# 2_MCU.net
KiCad netlist of a schematic drawn in Altium Designer
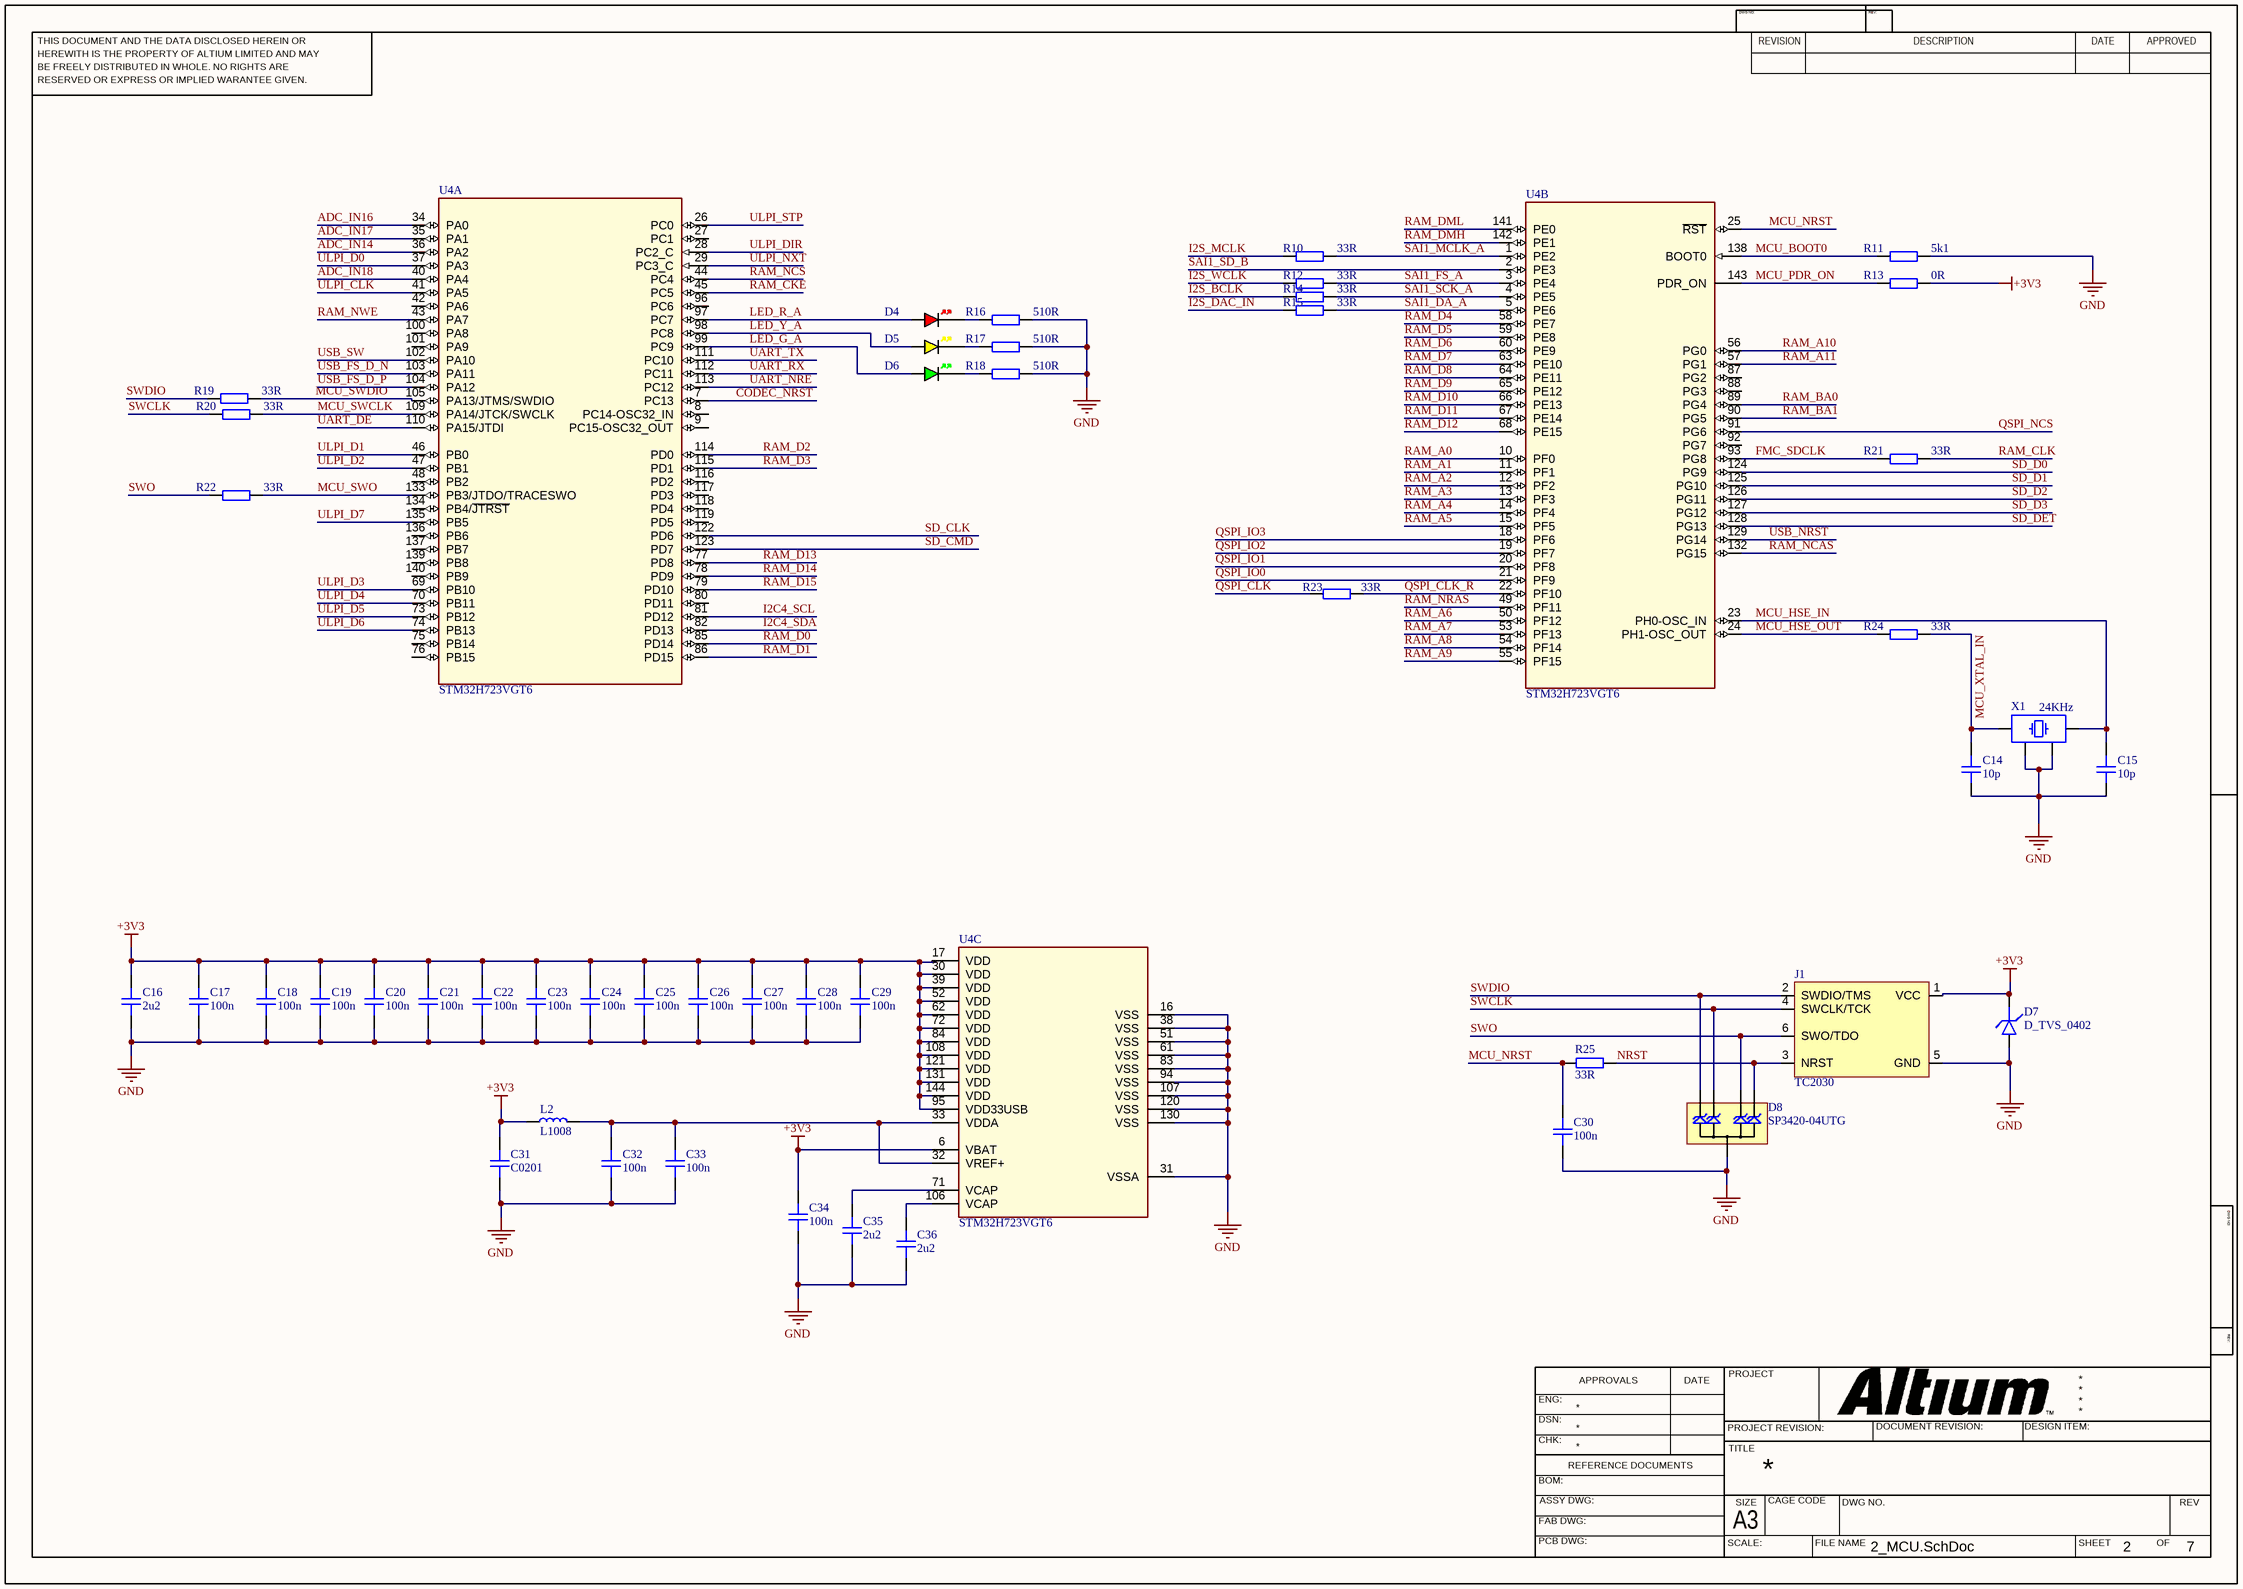
[diagram p0: 2_MCU.SchDoc]

(export (version "E")
  (design (tool "Eeschema 10.0.6"))
  (components
    (comp (ref "C14")
      (value "10p")
      (footprint "CAP_0201")
      (description "Capacitor SMD 0201")
      (libsource (lib "Schematic-Lib-PhilsLab") (part "CAP_0201"))
    )
    (comp (ref "C15")
      (value "10p")
      (footprint "CAP_0201")
      (description "Capacitor SMD 0201")
      (libsource (lib "Schematic-Lib-PhilsLab") (part "CAP_0201"))
    )
    (comp (ref "C16")
      (value "2u2")
      (footprint "CAP_0201")
      (description "Capacitor SMD 0201")
      (libsource (lib "Schematic-Lib-PhilsLab") (part "CAP_0201"))
    )
    (comp (ref "C17")
      (value "100n")
      (footprint "CAP_0201")
      (description "Capacitor SMD 0201")
      (libsource (lib "Schematic-Lib-PhilsLab") (part "CAP_0201"))
    )
    (comp (ref "C18")
      (value "100n")
      (footprint "CAP_0201")
      (description "Capacitor SMD 0201")
      (libsource (lib "Schematic-Lib-PhilsLab") (part "CAP_0201"))
    )
    (comp (ref "C19")
      (value "100n")
      (footprint "CAP_0201")
      (description "Capacitor SMD 0201")
      (libsource (lib "Schematic-Lib-PhilsLab") (part "CAP_0201"))
    )
    (comp (ref "C20")
      (value "100n")
      (footprint "CAP_0201")
      (description "Capacitor SMD 0201")
      (libsource (lib "Schematic-Lib-PhilsLab") (part "CAP_0201"))
    )
    (comp (ref "C21")
      (value "100n")
      (footprint "CAP_0201")
      (description "Capacitor SMD 0201")
      (libsource (lib "Schematic-Lib-PhilsLab") (part "CAP_0201"))
    )
    (comp (ref "C22")
      (value "100n")
      (footprint "CAP_0201")
      (description "Capacitor SMD 0201")
      (libsource (lib "Schematic-Lib-PhilsLab") (part "CAP_0201"))
    )
    (comp (ref "C23")
      (value "100n")
      (footprint "CAP_0201")
      (description "Capacitor SMD 0201")
      (libsource (lib "Schematic-Lib-PhilsLab") (part "CAP_0201"))
    )
    (comp (ref "C24")
      (value "100n")
      (footprint "CAP_0201")
      (description "Capacitor SMD 0201")
      (libsource (lib "Schematic-Lib-PhilsLab") (part "CAP_0201"))
    )
    (comp (ref "C25")
      (value "100n")
      (footprint "CAP_0201")
      (description "Capacitor SMD 0201")
      (libsource (lib "Schematic-Lib-PhilsLab") (part "CAP_0201"))
    )
    (comp (ref "C26")
      (value "100n")
      (footprint "CAP_0201")
      (description "Capacitor SMD 0201")
      (libsource (lib "Schematic-Lib-PhilsLab") (part "CAP_0201"))
    )
    (comp (ref "C27")
      (value "100n")
      (footprint "CAP_0201")
      (description "Capacitor SMD 0201")
      (libsource (lib "Schematic-Lib-PhilsLab") (part "CAP_0201"))
    )
    (comp (ref "C28")
      (value "100n")
      (footprint "CAP_0201")
      (description "Capacitor SMD 0201")
      (libsource (lib "Schematic-Lib-PhilsLab") (part "CAP_0201"))
    )
    (comp (ref "C29")
      (value "100n")
      (footprint "CAP_0201")
      (description "Capacitor SMD 0201")
      (libsource (lib "Schematic-Lib-PhilsLab") (part "CAP_0201"))
    )
    (comp (ref "C30")
      (value "100n")
      (footprint "CAP_0201")
      (description "Capacitor SMD 0201")
      (libsource (lib "Schematic-Lib-PhilsLab") (part "CAP_0201"))
    )
    (comp (ref "C31")
      (value "C0201")
      (footprint "CAP_0201")
      (description "Capacitor SMD 0201")
      (libsource (lib "Schematic-Lib-PhilsLab") (part "CAP_0201"))
    )
    (comp (ref "C32")
      (value "100n")
      (footprint "CAP_0201")
      (description "Capacitor SMD 0201")
      (libsource (lib "Schematic-Lib-PhilsLab") (part "CAP_0201"))
    )
    (comp (ref "C33")
      (value "100n")
      (footprint "CAP_0201")
      (description "Capacitor SMD 0201")
      (libsource (lib "Schematic-Lib-PhilsLab") (part "CAP_0201"))
    )
    (comp (ref "C34")
      (value "100n")
      (footprint "CAP_0201")
      (description "Capacitor SMD 0201")
      (libsource (lib "Schematic-Lib-PhilsLab") (part "CAP_0201"))
    )
    (comp (ref "C35")
      (value "2u2")
      (footprint "CAP_0201")
      (description "Capacitor SMD 0201")
      (libsource (lib "Schematic-Lib-PhilsLab") (part "CAP_0201"))
    )
    (comp (ref "C36")
      (value "2u2")
      (footprint "CAP_0201")
      (description "Capacitor SMD 0201")
      (libsource (lib "Schematic-Lib-PhilsLab") (part "CAP_0201"))
    )
    (comp (ref "D4")
      (value "RED")
      (footprint "LED_0603_RED")
      (description "LED 0603 RED SMD")
      (libsource (lib "Schematic-Lib-PhilsLab") (part "LED_0603_RED"))
    )
    (comp (ref "D5")
      (value "YELLOW")
      (footprint "LED_0603_YELLOW")
      (description "LED 0603 YELLOW SMD")
      (libsource (lib "Schematic-Lib-PhilsLab") (part "LED_0603_YELLOW"))
    )
    (comp (ref "D6")
      (value "GREEN")
      (footprint "LED_0603_GREEN")
      (description "LED 0603 GREEN SMD")
      (libsource (lib "Schematic-Lib-PhilsLab") (part "LED_0603_GREEN"))
    )
    (comp (ref "D7")
      (value "D_TVS_0402")
      (footprint "D_0402")
      (description "Diode TVS / ESD 0402")
      (libsource (lib "Schematic-Lib-PhilsLab") (part "D_TVS_0402"))
    )
    (comp (ref "D8")
      (value "SP3420-04UTG")
      (footprint "uDFN-10")
      (description "TVS Diode Array Low Capacitance ESD Protection 4-Channel (Vwork=3V3, Vclamp=6V)")
      (fields (field (name "MANUFACTURER") "Littelfuse"))
      (libsource (lib "Schematic-Lib-PhilsLab") (part "SP3420-04UTG"))
    )
    (comp (ref "J1")
      (value "TC2030")
      (footprint "TC2030-FP")
      (description "Tag-Connect No-Solder SWD Debug Connector DO NOT PLACE")
      (fields (field (name "MANUFACTURER") "Tag-Connect"))
      (libsource (lib "Schematic-Lib-PhilsLab") (part "TC2030"))
    )
    (comp (ref "L2")
      (value "L1008")
      (footprint "IND_1008")
      (description "Inductor SMD 1008")
      (libsource (lib "Schematic-Lib-PhilsLab") (part "IND_1008"))
    )
    (comp (ref "R10")
      (value "33R")
      (footprint "RES_0402")
      (description "Resistor SMD 0402")
      (libsource (lib "Schematic-Lib-PhilsLab") (part "RES_0402"))
    )
    (comp (ref "R11")
      (value "5k1")
      (footprint "RES_0402")
      (description "Resistor SMD 0402")
      (libsource (lib "Schematic-Lib-PhilsLab") (part "RES_0402"))
    )
    (comp (ref "R12")
      (value "33R")
      (footprint "RES_0402")
      (description "Resistor SMD 0402")
      (libsource (lib "Schematic-Lib-PhilsLab") (part "RES_0402"))
    )
    (comp (ref "R13")
      (value "0R")
      (footprint "RES_0402")
      (description "Resistor SMD 0402")
      (libsource (lib "Schematic-Lib-PhilsLab") (part "RES_0402"))
    )
    (comp (ref "R14")
      (value "33R")
      (footprint "RES_0402")
      (description "Resistor SMD 0402")
      (libsource (lib "Schematic-Lib-PhilsLab") (part "RES_0402"))
    )
    (comp (ref "R15")
      (value "33R")
      (footprint "RES_0402")
      (description "Resistor SMD 0402")
      (libsource (lib "Schematic-Lib-PhilsLab") (part "RES_0402"))
    )
    (comp (ref "R16")
      (value "510R")
      (footprint "RES_0402")
      (description "Resistor SMD 0402")
      (libsource (lib "Schematic-Lib-PhilsLab") (part "RES_0402"))
    )
    (comp (ref "R17")
      (value "510R")
      (footprint "RES_0402")
      (description "Resistor SMD 0402")
      (libsource (lib "Schematic-Lib-PhilsLab") (part "RES_0402"))
    )
    (comp (ref "R18")
      (value "510R")
      (footprint "RES_0402")
      (description "Resistor SMD 0402")
      (libsource (lib "Schematic-Lib-PhilsLab") (part "RES_0402"))
    )
    (comp (ref "R19")
      (value "33R")
      (footprint "RES_0402")
      (description "Resistor SMD 0402")
      (libsource (lib "Schematic-Lib-PhilsLab") (part "RES_0402"))
    )
    (comp (ref "R20")
      (value "33R")
      (footprint "RES_0402")
      (description "Resistor SMD 0402")
      (libsource (lib "Schematic-Lib-PhilsLab") (part "RES_0402"))
    )
    (comp (ref "R21")
      (value "33R")
      (footprint "RES_0402")
      (description "Resistor SMD 0402")
      (libsource (lib "Schematic-Lib-PhilsLab") (part "RES_0402"))
    )
    (comp (ref "R22")
      (value "33R")
      (footprint "RES_0402")
      (description "Resistor SMD 0402")
      (libsource (lib "Schematic-Lib-PhilsLab") (part "RES_0402"))
    )
    (comp (ref "R23")
      (value "33R")
      (footprint "RES_0402")
      (description "Resistor SMD 0402")
      (libsource (lib "Schematic-Lib-PhilsLab") (part "RES_0402"))
    )
    (comp (ref "R24")
      (value "33R")
      (footprint "RES_0402")
      (description "Resistor SMD 0402")
      (libsource (lib "Schematic-Lib-PhilsLab") (part "RES_0402"))
    )
    (comp (ref "R25")
      (value "33R")
      (footprint "RES_0402")
      (description "Resistor SMD 0402")
      (libsource (lib "Schematic-Lib-PhilsLab") (part "RES_0402"))
    )
    (comp (ref "U4")
      (value "STM32H723VGT6")
      (footprint "STM32H7")
      (libsource (lib "") (part "STM32H723VGT6_1"))
    )
    (comp (ref "X1")
      (value "24KHz")
      (footprint "XTAL_2520")
      (description "Crystal SMD 2520")
      (libsource (lib "Schematic-Lib-PhilsLab") (part "XTAL_2520"))
    )
  )
  (nets
    (net (code "1") (name "+3V3") (class "Default")
      (node (ref "C16") (pin "2") (pinfunction "2_2") (pintype "passive"))
      (node (ref "C17") (pin "2") (pinfunction "2_2") (pintype "passive"))
      (node (ref "C18") (pin "2") (pinfunction "2_2") (pintype "passive"))
      (node (ref "C19") (pin "2") (pinfunction "2_2") (pintype "passive"))
      (node (ref "C20") (pin "2") (pinfunction "2_2") (pintype "passive"))
      (node (ref "C21") (pin "2") (pinfunction "2_2") (pintype "passive"))
      (node (ref "C22") (pin "2") (pinfunction "2_2") (pintype "passive"))
      (node (ref "C23") (pin "2") (pinfunction "2_2") (pintype "passive"))
      (node (ref "C24") (pin "2") (pinfunction "2_2") (pintype "passive"))
      (node (ref "C25") (pin "2") (pinfunction "2_2") (pintype "passive"))
      (node (ref "C26") (pin "2") (pinfunction "2_2") (pintype "passive"))
      (node (ref "C27") (pin "2") (pinfunction "2_2") (pintype "passive"))
      (node (ref "C28") (pin "2") (pinfunction "2_2") (pintype "passive"))
      (node (ref "C29") (pin "2") (pinfunction "2_2") (pintype "passive"))
      (node (ref "C31") (pin "2") (pinfunction "2_2") (pintype "passive"))
      (node (ref "C34") (pin "2") (pinfunction "2_2") (pintype "passive"))
      (node (ref "D7") (pin "K") (pinfunction "K_K") (pintype "passive"))
      (node (ref "J1") (pin "1") (pinfunction "VCC_1") (pintype "passive"))
      (node (ref "L2") (pin "1") (pinfunction "1_1") (pintype "passive"))
      (node (ref "R13") (pin "2") (pinfunction "2_2") (pintype "passive"))
      (node (ref "U4") (pin "108") (pinfunction "VDD_108") (pintype "power_in"))
      (node (ref "U4") (pin "121") (pinfunction "VDD_121") (pintype "power_in"))
      (node (ref "U4") (pin "131") (pinfunction "VDD_131") (pintype "power_in"))
      (node (ref "U4") (pin "144") (pinfunction "VDD_144") (pintype "power_in"))
      (node (ref "U4") (pin "30") (pinfunction "VDD_30") (pintype "power_in"))
      (node (ref "U4") (pin "39") (pinfunction "VDD_39") (pintype "power_in"))
      (node (ref "U4") (pin "52") (pinfunction "VDD_52") (pintype "power_in"))
      (node (ref "U4") (pin "6") (pinfunction "VBAT_6") (pintype "power_in"))
      (node (ref "U4") (pin "62") (pinfunction "VDD_62") (pintype "power_in"))
      (node (ref "U4") (pin "72") (pinfunction "VDD_72") (pintype "power_in"))
      (node (ref "U4") (pin "84") (pinfunction "VDD_84") (pintype "power_in"))
      (node (ref "U4") (pin "95") (pinfunction "VDD33USB_95") (pintype "power_in"))
    )
    (net (code "2") (name "/ADC_IN14") (class "Default")
      (node (ref "U4") (pin "36") (pinfunction "PA2_36") (pintype "bidirectional"))
    )
    (net (code "3") (name "/ADC_IN16") (class "Default")
      (node (ref "U4") (pin "34") (pinfunction "PA0_34") (pintype "bidirectional"))
    )
    (net (code "4") (name "/ADC_IN17") (class "Default")
      (node (ref "U4") (pin "35") (pinfunction "PA1_35") (pintype "bidirectional"))
    )
    (net (code "5") (name "/ADC_IN18") (class "Default")
      (node (ref "U4") (pin "40") (pinfunction "PA4_40") (pintype "bidirectional"))
    )
    (net (code "6") (name "/CODEC_NRST") (class "Default")
      (node (ref "U4") (pin "7") (pinfunction "PC13_7") (pintype "bidirectional"))
    )
    (net (code "7") (name "/FMC_SDCLK") (class "Default")
      (node (ref "R21") (pin "1") (pinfunction "1_1") (pintype "passive"))
      (node (ref "U4") (pin "93") (pinfunction "PG8_93") (pintype "bidirectional"))
    )
    (net (code "8") (name "/I2C4_SCL") (class "Default")
      (node (ref "U4") (pin "81") (pinfunction "PD12_81") (pintype "bidirectional"))
    )
    (net (code "9") (name "/I2C4_SDA") (class "Default")
      (node (ref "U4") (pin "82") (pinfunction "PD13_82") (pintype "bidirectional"))
    )
    (net (code "10") (name "/I2S_BCLK") (class "Default")
      (node (ref "R14") (pin "1") (pinfunction "1_1") (pintype "passive"))
    )
    (net (code "11") (name "/I2S_DAC_IN") (class "Default")
      (node (ref "R15") (pin "1") (pinfunction "1_1") (pintype "passive"))
    )
    (net (code "12") (name "/I2S_MCLK") (class "Default")
      (node (ref "R10") (pin "1") (pinfunction "1_1") (pintype "passive"))
    )
    (net (code "13") (name "/I2S_WCLK") (class "Default")
      (node (ref "R12") (pin "1") (pinfunction "1_1") (pintype "passive"))
    )
    (net (code "14") (name "/LED_G_A") (class "Default")
      (node (ref "D6") (pin "A") (pinfunction "A_A") (pintype "passive"))
      (node (ref "U4") (pin "99") (pinfunction "PC9_99") (pintype "bidirectional"))
    )
    (net (code "15") (name "/LED_R_A") (class "Default")
      (node (ref "D4") (pin "A") (pinfunction "A_A") (pintype "passive"))
      (node (ref "U4") (pin "97") (pinfunction "PC7_97") (pintype "bidirectional"))
    )
    (net (code "16") (name "/LED_Y_A") (class "Default")
      (node (ref "D5") (pin "A") (pinfunction "A_A") (pintype "passive"))
      (node (ref "U4") (pin "98") (pinfunction "PC8_98") (pintype "bidirectional"))
    )
    (net (code "17") (name "/MCU_BOOT0") (class "Default")
      (node (ref "R11") (pin "1") (pinfunction "1_1") (pintype "passive"))
      (node (ref "U4") (pin "138") (pinfunction "BOOT0_138") (pintype "input"))
    )
    (net (code "18") (name "/MCU_HSE_IN") (class "Default")
      (node (ref "C15") (pin "2") (pinfunction "2_2") (pintype "passive"))
      (node (ref "U4") (pin "23") (pinfunction "PH0-OSC_IN_23") (pintype "bidirectional"))
      (node (ref "X1") (pin "3") (pinfunction "3_3") (pintype "passive"))
    )
    (net (code "19") (name "/MCU_HSE_OUT") (class "Default")
      (node (ref "R24") (pin "1") (pinfunction "1_1") (pintype "passive"))
      (node (ref "U4") (pin "24") (pinfunction "PH1-OSC_OUT_24") (pintype "bidirectional"))
    )
    (net (code "20") (name "/MCU_NRST") (class "Default")
      (node (ref "C30") (pin "2") (pinfunction "2_2") (pintype "passive"))
      (node (ref "R25") (pin "1") (pinfunction "1_1") (pintype "passive"))
      (node (ref "U4") (pin "25") (pinfunction "~{RST}_25") (pintype "bidirectional"))
    )
    (net (code "21") (name "/MCU_PDR_ON") (class "Default")
      (node (ref "R13") (pin "1") (pinfunction "1_1") (pintype "passive"))
      (node (ref "U4") (pin "143") (pinfunction "PDR_ON_143") (pintype "power_in"))
    )
    (net (code "22") (name "/MCU_SWCLK") (class "Default")
      (node (ref "R20") (pin "2") (pinfunction "2_2") (pintype "passive"))
      (node (ref "U4") (pin "109") (pinfunction "PA14/JTCK/SWCLK_109") (pintype "bidirectional"))
    )
    (net (code "23") (name "/MCU_SWDIO") (class "Default")
      (node (ref "R19") (pin "2") (pinfunction "2_2") (pintype "passive"))
      (node (ref "U4") (pin "105") (pinfunction "PA13/JTMS/SWDIO_105") (pintype "bidirectional"))
    )
    (net (code "24") (name "/MCU_SWO") (class "Default")
      (node (ref "R22") (pin "2") (pinfunction "2_2") (pintype "passive"))
      (node (ref "U4") (pin "133") (pinfunction "PB3/JTDO/TRACESWO_133") (pintype "bidirectional"))
    )
    (net (code "25") (name "/MCU_XTAL_IN") (class "Default")
      (node (ref "C14") (pin "2") (pinfunction "2_2") (pintype "passive"))
      (node (ref "R24") (pin "2") (pinfunction "2_2") (pintype "passive"))
      (node (ref "X1") (pin "1") (pinfunction "1_1") (pintype "passive"))
    )
    (net (code "26") (name "/NRST") (class "Default")
      (node (ref "D8") (pin "56") (pintype "passive"))
      (node (ref "J1") (pin "3") (pinfunction "NRST_3") (pintype "passive"))
      (node (ref "R25") (pin "2") (pinfunction "2_2") (pintype "passive"))
    )
    (net (code "27") (name "/QSPI_CLK") (class "Default")
      (node (ref "R23") (pin "1") (pinfunction "1_1") (pintype "passive"))
    )
    (net (code "28") (name "/QSPI_CLK_R") (class "Default")
      (node (ref "R23") (pin "2") (pinfunction "2_2") (pintype "passive"))
      (node (ref "U4") (pin "22") (pinfunction "PF10_22") (pintype "bidirectional"))
    )
    (net (code "29") (name "/QSPI_IO0") (class "Default")
      (node (ref "U4") (pin "21") (pinfunction "PF9_21") (pintype "bidirectional"))
    )
    (net (code "30") (name "/QSPI_IO1") (class "Default")
      (node (ref "U4") (pin "20") (pinfunction "PF8_20") (pintype "bidirectional"))
    )
    (net (code "31") (name "/QSPI_IO2") (class "Default")
      (node (ref "U4") (pin "19") (pinfunction "PF7_19") (pintype "bidirectional"))
    )
    (net (code "32") (name "/QSPI_IO3") (class "Default")
      (node (ref "U4") (pin "18") (pinfunction "PF6_18") (pintype "bidirectional"))
    )
    (net (code "33") (name "/QSPI_NCS") (class "Default")
      (node (ref "U4") (pin "91") (pinfunction "PG6_91") (pintype "bidirectional"))
    )
    (net (code "34") (name "/RAM_A0") (class "Default")
      (node (ref "U4") (pin "10") (pinfunction "PF0_10") (pintype "bidirectional"))
    )
    (net (code "35") (name "/RAM_A1") (class "Default")
      (node (ref "U4") (pin "11") (pinfunction "PF1_11") (pintype "bidirectional"))
    )
    (net (code "36") (name "/RAM_A2") (class "Default")
      (node (ref "U4") (pin "12") (pinfunction "PF2_12") (pintype "bidirectional"))
    )
    (net (code "37") (name "/RAM_A3") (class "Default")
      (node (ref "U4") (pin "13") (pinfunction "PF3_13") (pintype "bidirectional"))
    )
    (net (code "38") (name "/RAM_A4") (class "Default")
      (node (ref "U4") (pin "14") (pinfunction "PF4_14") (pintype "bidirectional"))
    )
    (net (code "39") (name "/RAM_A5") (class "Default")
      (node (ref "U4") (pin "15") (pinfunction "PF5_15") (pintype "bidirectional"))
    )
    (net (code "40") (name "/RAM_A6") (class "Default")
      (node (ref "U4") (pin "50") (pinfunction "PF12_50") (pintype "bidirectional"))
    )
    (net (code "41") (name "/RAM_A7") (class "Default")
      (node (ref "U4") (pin "53") (pinfunction "PF13_53") (pintype "bidirectional"))
    )
    (net (code "42") (name "/RAM_A8") (class "Default")
      (node (ref "U4") (pin "54") (pinfunction "PF14_54") (pintype "bidirectional"))
    )
    (net (code "43") (name "/RAM_A9") (class "Default")
      (node (ref "U4") (pin "55") (pinfunction "PF15_55") (pintype "bidirectional"))
    )
    (net (code "44") (name "/RAM_A10") (class "Default")
      (node (ref "U4") (pin "56") (pinfunction "PG0_56") (pintype "bidirectional"))
    )
    (net (code "45") (name "/RAM_A11") (class "Default")
      (node (ref "U4") (pin "57") (pinfunction "PG1_57") (pintype "bidirectional"))
    )
    (net (code "46") (name "/RAM_BA0") (class "Default")
      (node (ref "U4") (pin "89") (pinfunction "PG4_89") (pintype "bidirectional"))
    )
    (net (code "47") (name "/RAM_BA1") (class "Default")
      (node (ref "U4") (pin "90") (pinfunction "PG5_90") (pintype "bidirectional"))
    )
    (net (code "48") (name "/RAM_CKE") (class "Default")
      (node (ref "U4") (pin "45") (pinfunction "PC5_45") (pintype "bidirectional"))
    )
    (net (code "49") (name "/RAM_CLK") (class "Default")
      (node (ref "R21") (pin "2") (pinfunction "2_2") (pintype "passive"))
    )
    (net (code "50") (name "/RAM_D0") (class "Default")
      (node (ref "U4") (pin "85") (pinfunction "PD14_85") (pintype "bidirectional"))
    )
    (net (code "51") (name "/RAM_D1") (class "Default")
      (node (ref "U4") (pin "86") (pinfunction "PD15_86") (pintype "bidirectional"))
    )
    (net (code "52") (name "/RAM_D2") (class "Default")
      (node (ref "U4") (pin "114") (pinfunction "PD0_114") (pintype "bidirectional"))
    )
    (net (code "53") (name "/RAM_D3") (class "Default")
      (node (ref "U4") (pin "115") (pinfunction "PD1_115") (pintype "bidirectional"))
    )
    (net (code "54") (name "/RAM_D4") (class "Default")
      (node (ref "U4") (pin "58") (pinfunction "PE7_58") (pintype "bidirectional"))
    )
    (net (code "55") (name "/RAM_D5") (class "Default")
      (node (ref "U4") (pin "59") (pinfunction "PE8_59") (pintype "bidirectional"))
    )
    (net (code "56") (name "/RAM_D6") (class "Default")
      (node (ref "U4") (pin "60") (pinfunction "PE9_60") (pintype "bidirectional"))
    )
    (net (code "57") (name "/RAM_D7") (class "Default")
      (node (ref "U4") (pin "63") (pinfunction "PE10_63") (pintype "bidirectional"))
    )
    (net (code "58") (name "/RAM_D8") (class "Default")
      (node (ref "U4") (pin "64") (pinfunction "PE11_64") (pintype "bidirectional"))
    )
    (net (code "59") (name "/RAM_D9") (class "Default")
      (node (ref "U4") (pin "65") (pinfunction "PE12_65") (pintype "bidirectional"))
    )
    (net (code "60") (name "/RAM_D10") (class "Default")
      (node (ref "U4") (pin "66") (pinfunction "PE13_66") (pintype "bidirectional"))
    )
    (net (code "61") (name "/RAM_D11") (class "Default")
      (node (ref "U4") (pin "67") (pinfunction "PE14_67") (pintype "bidirectional"))
    )
    (net (code "62") (name "/RAM_D12") (class "Default")
      (node (ref "U4") (pin "68") (pinfunction "PE15_68") (pintype "bidirectional"))
    )
    (net (code "63") (name "/RAM_D13") (class "Default")
      (node (ref "U4") (pin "77") (pinfunction "PD8_77") (pintype "bidirectional"))
    )
    (net (code "64") (name "/RAM_D14") (class "Default")
      (node (ref "U4") (pin "78") (pinfunction "PD9_78") (pintype "bidirectional"))
    )
    (net (code "65") (name "/RAM_D15") (class "Default")
      (node (ref "U4") (pin "79") (pinfunction "PD10_79") (pintype "bidirectional"))
    )
    (net (code "66") (name "/RAM_DMH") (class "Default")
      (node (ref "U4") (pin "142") (pinfunction "PE1_142") (pintype "bidirectional"))
    )
    (net (code "67") (name "/RAM_DML") (class "Default")
      (node (ref "U4") (pin "141") (pinfunction "PE0_141") (pintype "bidirectional"))
    )
    (net (code "68") (name "/RAM_NCAS") (class "Default")
      (node (ref "U4") (pin "132") (pinfunction "PG15_132") (pintype "bidirectional"))
    )
    (net (code "69") (name "/RAM_NCS") (class "Default")
      (node (ref "U4") (pin "44") (pinfunction "PC4_44") (pintype "bidirectional"))
    )
    (net (code "70") (name "/RAM_NRAS") (class "Default")
      (node (ref "U4") (pin "49") (pinfunction "PF11_49") (pintype "bidirectional"))
    )
    (net (code "71") (name "/RAM_NWE") (class "Default")
      (node (ref "U4") (pin "43") (pinfunction "PA7_43") (pintype "bidirectional"))
    )
    (net (code "72") (name "/SAI1_DA_A") (class "Default")
      (node (ref "R15") (pin "2") (pinfunction "2_2") (pintype "passive"))
      (node (ref "U4") (pin "5") (pinfunction "PE6_5") (pintype "bidirectional"))
    )
    (net (code "73") (name "/SAI1_FS_A") (class "Default")
      (node (ref "R12") (pin "2") (pinfunction "2_2") (pintype "passive"))
      (node (ref "U4") (pin "3") (pinfunction "PE4_3") (pintype "bidirectional"))
    )
    (net (code "74") (name "/SAI1_MCLK_A") (class "Default")
      (node (ref "R10") (pin "2") (pinfunction "2_2") (pintype "passive"))
      (node (ref "U4") (pin "1") (pinfunction "PE2_1") (pintype "bidirectional"))
    )
    (net (code "75") (name "/SAI1_SCK_A") (class "Default")
      (node (ref "R14") (pin "2") (pinfunction "2_2") (pintype "passive"))
      (node (ref "U4") (pin "4") (pinfunction "PE5_4") (pintype "bidirectional"))
    )
    (net (code "76") (name "/SAI1_SD_B") (class "Default")
      (node (ref "U4") (pin "2") (pinfunction "PE3_2") (pintype "bidirectional"))
    )
    (net (code "77") (name "/SD_CLK") (class "Default")
      (node (ref "U4") (pin "122") (pinfunction "PD6_122") (pintype "bidirectional"))
    )
    (net (code "78") (name "/SD_CMD") (class "Default")
      (node (ref "U4") (pin "123") (pinfunction "PD7_123") (pintype "bidirectional"))
    )
    (net (code "79") (name "/SD_D0") (class "Default")
      (node (ref "U4") (pin "124") (pinfunction "PG9_124") (pintype "bidirectional"))
    )
    (net (code "80") (name "/SD_D1") (class "Default")
      (node (ref "U4") (pin "125") (pinfunction "PG10_125") (pintype "bidirectional"))
    )
    (net (code "81") (name "/SD_D2") (class "Default")
      (node (ref "U4") (pin "126") (pinfunction "PG11_126") (pintype "bidirectional"))
    )
    (net (code "82") (name "/SD_D3") (class "Default")
      (node (ref "U4") (pin "127") (pinfunction "PG12_127") (pintype "bidirectional"))
    )
    (net (code "83") (name "/SD_DET") (class "Default")
      (node (ref "U4") (pin "128") (pinfunction "PG13_128") (pintype "bidirectional"))
    )
    (net (code "84") (name "/SWCLK") (class "Default")
      (node (ref "D8") (pin "29") (pintype "passive"))
      (node (ref "J1") (pin "4") (pinfunction "SWCLK/TCK_4") (pintype "passive"))
      (node (ref "R20") (pin "1") (pinfunction "1_1") (pintype "passive"))
    )
    (net (code "85") (name "/SWDIO") (class "Default")
      (node (ref "D8") (pin "110") (pintype "passive"))
      (node (ref "J1") (pin "2") (pinfunction "SWDIO/TMS_2") (pintype "passive"))
      (node (ref "R19") (pin "1") (pinfunction "1_1") (pintype "passive"))
    )
    (net (code "86") (name "/SWO") (class "Default")
      (node (ref "D8") (pin "47") (pintype "passive"))
      (node (ref "J1") (pin "6") (pinfunction "SWO/TDO_6") (pintype "passive"))
      (node (ref "R22") (pin "1") (pinfunction "1_1") (pintype "passive"))
    )
    (net (code "87") (name "/UART_DE") (class "Default")
      (node (ref "U4") (pin "110") (pinfunction "PA15/JTDI_110") (pintype "bidirectional"))
    )
    (net (code "88") (name "/UART_NRE") (class "Default")
      (node (ref "U4") (pin "113") (pinfunction "PC12_113") (pintype "bidirectional"))
    )
    (net (code "89") (name "/UART_RX") (class "Default")
      (node (ref "U4") (pin "112") (pinfunction "PC11_112") (pintype "bidirectional"))
    )
    (net (code "90") (name "/UART_TX") (class "Default")
      (node (ref "U4") (pin "111") (pinfunction "PC10_111") (pintype "bidirectional"))
    )
    (net (code "91") (name "/ULPI_CLK") (class "Default")
      (node (ref "U4") (pin "41") (pinfunction "PA5_41") (pintype "bidirectional"))
    )
    (net (code "92") (name "/ULPI_D0") (class "Default")
      (node (ref "U4") (pin "37") (pinfunction "PA3_37") (pintype "bidirectional"))
    )
    (net (code "93") (name "/ULPI_D1") (class "Default")
      (node (ref "U4") (pin "46") (pinfunction "PB0_46") (pintype "bidirectional"))
    )
    (net (code "94") (name "/ULPI_D2") (class "Default")
      (node (ref "U4") (pin "47") (pinfunction "PB1_47") (pintype "bidirectional"))
    )
    (net (code "95") (name "/ULPI_D3") (class "Default")
      (node (ref "U4") (pin "69") (pinfunction "PB10_69") (pintype "bidirectional"))
    )
    (net (code "96") (name "/ULPI_D4") (class "Default")
      (node (ref "U4") (pin "70") (pinfunction "PB11_70") (pintype "bidirectional"))
    )
    (net (code "97") (name "/ULPI_D5") (class "Default")
      (node (ref "U4") (pin "73") (pinfunction "PB12_73") (pintype "bidirectional"))
    )
    (net (code "98") (name "/ULPI_D6") (class "Default")
      (node (ref "U4") (pin "74") (pinfunction "PB13_74") (pintype "bidirectional"))
    )
    (net (code "99") (name "/ULPI_D7") (class "Default")
      (node (ref "U4") (pin "135") (pinfunction "PB5_135") (pintype "bidirectional"))
    )
    (net (code "100") (name "/ULPI_DIR") (class "Default")
      (node (ref "U4") (pin "28") (pinfunction "PC2_C_28") (pintype "input"))
    )
    (net (code "101") (name "/ULPI_NXT") (class "Default")
      (node (ref "U4") (pin "29") (pinfunction "PC3_C_29") (pintype "input"))
    )
    (net (code "102") (name "/ULPI_STP") (class "Default")
      (node (ref "U4") (pin "26") (pinfunction "PC0_26") (pintype "bidirectional"))
    )
    (net (code "103") (name "/USB_FS_D_N") (class "Default")
      (node (ref "U4") (pin "103") (pinfunction "PA11_103") (pintype "bidirectional"))
    )
    (net (code "104") (name "/USB_FS_D_P") (class "Default")
      (node (ref "U4") (pin "104") (pinfunction "PA12_104") (pintype "bidirectional"))
    )
    (net (code "105") (name "/USB_NRST") (class "Default")
      (node (ref "U4") (pin "129") (pinfunction "PG14_129") (pintype "bidirectional"))
    )
    (net (code "106") (name "/USB_SW") (class "Default")
      (node (ref "U4") (pin "102") (pinfunction "PA10_102") (pintype "bidirectional"))
    )
    (net (code "107") (name "GND") (class "Default")
      (node (ref "C14") (pin "1") (pinfunction "1_1") (pintype "passive"))
      (node (ref "C15") (pin "1") (pinfunction "1_1") (pintype "passive"))
      (node (ref "C16") (pin "1") (pinfunction "1_1") (pintype "passive"))
      (node (ref "C17") (pin "1") (pinfunction "1_1") (pintype "passive"))
      (node (ref "C18") (pin "1") (pinfunction "1_1") (pintype "passive"))
      (node (ref "C19") (pin "1") (pinfunction "1_1") (pintype "passive"))
      (node (ref "C20") (pin "1") (pinfunction "1_1") (pintype "passive"))
      (node (ref "C21") (pin "1") (pinfunction "1_1") (pintype "passive"))
      (node (ref "C22") (pin "1") (pinfunction "1_1") (pintype "passive"))
      (node (ref "C23") (pin "1") (pinfunction "1_1") (pintype "passive"))
      (node (ref "C24") (pin "1") (pinfunction "1_1") (pintype "passive"))
      (node (ref "C25") (pin "1") (pinfunction "1_1") (pintype "passive"))
      (node (ref "C26") (pin "1") (pinfunction "1_1") (pintype "passive"))
      (node (ref "C27") (pin "1") (pinfunction "1_1") (pintype "passive"))
      (node (ref "C28") (pin "1") (pinfunction "1_1") (pintype "passive"))
      (node (ref "C29") (pin "1") (pinfunction "1_1") (pintype "passive"))
      (node (ref "C30") (pin "1") (pinfunction "1_1") (pintype "passive"))
      (node (ref "C31") (pin "1") (pinfunction "1_1") (pintype "passive"))
      (node (ref "C32") (pin "1") (pinfunction "1_1") (pintype "passive"))
      (node (ref "C33") (pin "1") (pinfunction "1_1") (pintype "passive"))
      (node (ref "C34") (pin "1") (pinfunction "1_1") (pintype "passive"))
      (node (ref "C35") (pin "1") (pinfunction "1_1") (pintype "passive"))
      (node (ref "C36") (pin "1") (pinfunction "1_1") (pintype "passive"))
      (node (ref "D7") (pin "A") (pinfunction "A_A") (pintype "passive"))
      (node (ref "D8") (pin "38") (pinfunction "GND_38") (pintype "passive"))
      (node (ref "J1") (pin "5") (pinfunction "GND_5") (pintype "passive"))
      (node (ref "R11") (pin "2") (pinfunction "2_2") (pintype "passive"))
      (node (ref "R16") (pin "2") (pinfunction "2_2") (pintype "passive"))
      (node (ref "R17") (pin "2") (pinfunction "2_2") (pintype "passive"))
      (node (ref "R18") (pin "2") (pinfunction "2_2") (pintype "passive"))
      (node (ref "U4") (pin "107") (pinfunction "VSS_107") (pintype "power_in"))
      (node (ref "U4") (pin "120") (pinfunction "VSS_120") (pintype "power_in"))
      (node (ref "U4") (pin "130") (pinfunction "VSS_130") (pintype "power_in"))
      (node (ref "U4") (pin "16") (pinfunction "VSS_16") (pintype "power_in"))
      (node (ref "U4") (pin "31") (pinfunction "VSSA_31") (pintype "power_in"))
      (node (ref "U4") (pin "38") (pinfunction "VSS_38") (pintype "power_in"))
      (node (ref "U4") (pin "51") (pinfunction "VSS_51") (pintype "power_in"))
      (node (ref "U4") (pin "61") (pinfunction "VSS_61") (pintype "power_in"))
      (node (ref "U4") (pin "83") (pinfunction "VSS_83") (pintype "power_in"))
      (node (ref "U4") (pin "94") (pinfunction "VSS_94") (pintype "power_in"))
      (node (ref "X1") (pin "2") (pinfunction "2_2") (pintype "passive"))
      (node (ref "X1") (pin "4") (pinfunction "4_4") (pintype "passive"))
    )
    (net (code "108") (name "Net-(C35-Pad2)") (class "Default")
      (node (ref "C35") (pin "2") (pinfunction "2_2") (pintype "passive"))
      (node (ref "U4") (pin "71") (pinfunction "VCAP_71") (pintype "power_in"))
    )
    (net (code "109") (name "Net-(C36-Pad2)") (class "Default")
      (node (ref "C36") (pin "2") (pinfunction "2_2") (pintype "passive"))
      (node (ref "U4") (pin "106") (pinfunction "VCAP_106") (pintype "power_in"))
    )
    (net (code "110") (name "Net-(D4-PadK)") (class "Default")
      (node (ref "D4") (pin "K") (pinfunction "K_K") (pintype "passive"))
      (node (ref "R16") (pin "1") (pinfunction "1_1") (pintype "passive"))
    )
    (net (code "111") (name "Net-(D5-PadK)") (class "Default")
      (node (ref "D5") (pin "K") (pinfunction "K_K") (pintype "passive"))
      (node (ref "R17") (pin "1") (pinfunction "1_1") (pintype "passive"))
    )
    (net (code "112") (name "Net-(D6-PadK)") (class "Default")
      (node (ref "D6") (pin "K") (pinfunction "K_K") (pintype "passive"))
      (node (ref "R18") (pin "1") (pinfunction "1_1") (pintype "passive"))
    )
    (net (code "113") (name "Net-(U4C-VDDA)") (class "Default")
      (node (ref "C32") (pin "2") (pinfunction "2_2") (pintype "passive"))
      (node (ref "C33") (pin "2") (pinfunction "2_2") (pintype "passive"))
      (node (ref "L2") (pin "2") (pinfunction "2_2") (pintype "passive"))
      (node (ref "U4") (pin "32") (pinfunction "VREF+_32") (pintype "power_in"))
      (node (ref "U4") (pin "33") (pinfunction "VDDA_33") (pintype "power_in"))
    )
    (net (code "114") (name "unconnected-(U4A-PA6-Pad42)") (class "Default")
      (node (ref "U4") (pin "42") (pinfunction "PA6_42") (pintype "bidirectional"))
    )
    (net (code "115") (name "unconnected-(U4A-PA8-Pad100)") (class "Default")
      (node (ref "U4") (pin "100") (pinfunction "PA8_100") (pintype "bidirectional"))
    )
    (net (code "116") (name "unconnected-(U4A-PA9-Pad101)") (class "Default")
      (node (ref "U4") (pin "101") (pinfunction "PA9_101") (pintype "bidirectional"))
    )
    (net (code "117") (name "unconnected-(U4A-PB2-Pad48)") (class "Default")
      (node (ref "U4") (pin "48") (pinfunction "PB2_48") (pintype "bidirectional"))
    )
    (net (code "118") (name "unconnected-(U4A-PB4{slash}~{JTRST}-Pad134)") (class "Default")
      (node (ref "U4") (pin "134") (pinfunction "PB4/~{JTRST}_134") (pintype "bidirectional"))
    )
    (net (code "119") (name "unconnected-(U4A-PB6-Pad136)") (class "Default")
      (node (ref "U4") (pin "136") (pinfunction "PB6_136") (pintype "bidirectional"))
    )
    (net (code "120") (name "unconnected-(U4A-PB7-Pad137)") (class "Default")
      (node (ref "U4") (pin "137") (pinfunction "PB7_137") (pintype "bidirectional"))
    )
    (net (code "121") (name "unconnected-(U4A-PB8-Pad139)") (class "Default")
      (node (ref "U4") (pin "139") (pinfunction "PB8_139") (pintype "bidirectional"))
    )
    (net (code "122") (name "unconnected-(U4A-PB9-Pad140)") (class "Default")
      (node (ref "U4") (pin "140") (pinfunction "PB9_140") (pintype "bidirectional"))
    )
    (net (code "123") (name "unconnected-(U4A-PB14-Pad75)") (class "Default")
      (node (ref "U4") (pin "75") (pinfunction "PB14_75") (pintype "bidirectional"))
    )
    (net (code "124") (name "unconnected-(U4A-PB15-Pad76)") (class "Default")
      (node (ref "U4") (pin "76") (pinfunction "PB15_76") (pintype "bidirectional"))
    )
    (net (code "125") (name "unconnected-(U4A-PC1-Pad27)") (class "Default")
      (node (ref "U4") (pin "27") (pinfunction "PC1_27") (pintype "bidirectional"))
    )
    (net (code "126") (name "unconnected-(U4A-PC6-Pad96)") (class "Default")
      (node (ref "U4") (pin "96") (pinfunction "PC6_96") (pintype "bidirectional"))
    )
    (net (code "127") (name "unconnected-(U4A-PC14-OSC32_IN-Pad8)") (class "Default")
      (node (ref "U4") (pin "8") (pinfunction "PC14-OSC32_IN_8") (pintype "bidirectional"))
    )
    (net (code "128") (name "unconnected-(U4A-PC15-OSC32_OUT-Pad9)") (class "Default")
      (node (ref "U4") (pin "9") (pinfunction "PC15-OSC32_OUT_9") (pintype "bidirectional"))
    )
    (net (code "129") (name "unconnected-(U4A-PD2-Pad116)") (class "Default")
      (node (ref "U4") (pin "116") (pinfunction "PD2_116") (pintype "bidirectional"))
    )
    (net (code "130") (name "unconnected-(U4A-PD3-Pad117)") (class "Default")
      (node (ref "U4") (pin "117") (pinfunction "PD3_117") (pintype "bidirectional"))
    )
    (net (code "131") (name "unconnected-(U4A-PD4-Pad118)") (class "Default")
      (node (ref "U4") (pin "118") (pinfunction "PD4_118") (pintype "bidirectional"))
    )
    (net (code "132") (name "unconnected-(U4A-PD5-Pad119)") (class "Default")
      (node (ref "U4") (pin "119") (pinfunction "PD5_119") (pintype "bidirectional"))
    )
    (net (code "133") (name "unconnected-(U4A-PD11-Pad80)") (class "Default")
      (node (ref "U4") (pin "80") (pinfunction "PD11_80") (pintype "bidirectional"))
    )
    (net (code "134") (name "unconnected-(U4B-PG2-Pad87)") (class "Default")
      (node (ref "U4") (pin "87") (pinfunction "PG2_87") (pintype "bidirectional"))
    )
    (net (code "135") (name "unconnected-(U4B-PG3-Pad88)") (class "Default")
      (node (ref "U4") (pin "88") (pinfunction "PG3_88") (pintype "bidirectional"))
    )
    (net (code "136") (name "unconnected-(U4B-PG7-Pad92)") (class "Default")
      (node (ref "U4") (pin "92") (pinfunction "PG7_92") (pintype "bidirectional"))
    )
    (net (code "137") (name "unconnected-(U4C-VDD-Pad17)") (class "Default")
      (node (ref "U4") (pin "17") (pinfunction "VDD_17") (pintype "power_in"))
    )
  )
)
